# trashotron-slimezistor.net
KiCad netlist of a schematic drawn in EAGLE
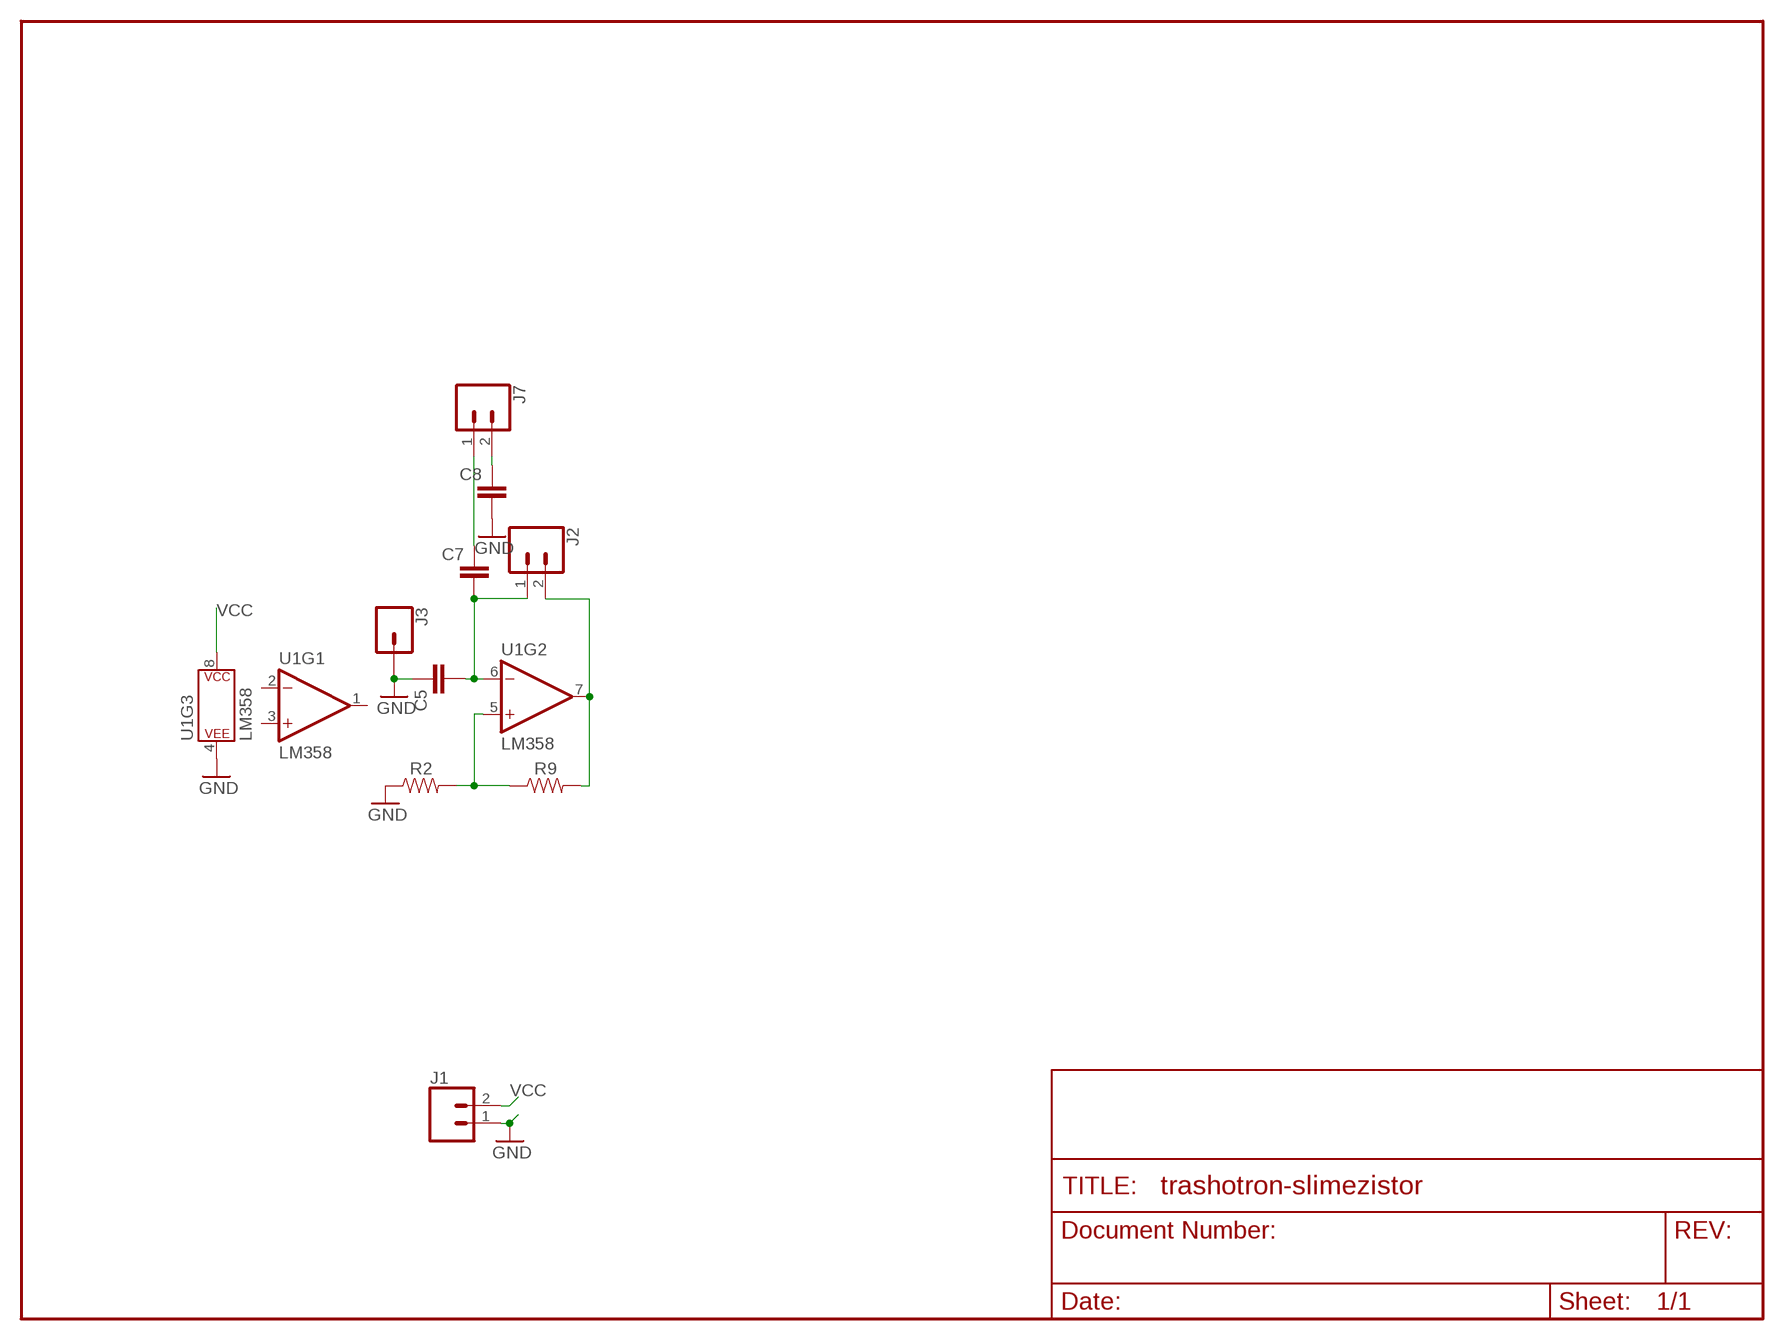
[diagram p0: schematic, sheet 1]

(export (version "E")
  (design (tool "Eeschema 10.0.6"))
  (components
    (comp (ref "C5")
      (value "C-EU050-050X075")
      (footprint "eagle-import:C050-050X075")
      (libsource (lib "eagle-import") (part "C-EU050-050X075"))
    )
    (comp (ref "C7")
      (value "C-EU050-050X075")
      (footprint "eagle-import:C050-050X075")
      (libsource (lib "eagle-import") (part "C-EU050-050X075"))
    )
    (comp (ref "C8")
      (value "C-EU050-050X075")
      (footprint "eagle-import:C050-050X075")
      (libsource (lib "eagle-import") (part "C-EU050-050X075"))
    )
    (comp (ref "J1")
      (value "CONN_02")
      (footprint "eagle-import:1X02")
      (libsource (lib "eagle-import") (part "CONN_02"))
    )
    (comp (ref "J2")
      (value "CONN_02")
      (footprint "eagle-import:1X02")
      (libsource (lib "eagle-import") (part "CONN_02"))
    )
    (comp (ref "J3")
      (value "CONN_01")
      (footprint "eagle-import:1X01")
      (libsource (lib "eagle-import") (part "CONN_01"))
    )
    (comp (ref "J7")
      (value "CONN_02")
      (footprint "eagle-import:1X02")
      (libsource (lib "eagle-import") (part "CONN_02"))
    )
    (comp (ref "R2")
      (value "RESISTORAXIAL-0.3")
      (footprint "eagle-import:AXIAL-0.3")
      (libsource (lib "eagle-import") (part "RESISTORAXIAL-0.3"))
    )
    (comp (ref "R9")
      (value "RESISTORAXIAL-0.3")
      (footprint "eagle-import:AXIAL-0.3")
      (libsource (lib "eagle-import") (part "RESISTORAXIAL-0.3"))
    )
    (comp (ref "U1")
      (value "LM358")
      (footprint "eagle-import:DIP08")
      (libsource (lib "eagle-import") (part "LM358"))
    )
  )
  (nets
    (net (code "1") (name "/VCC") (class "Default")
      (node (ref "J1") (pin "2") (pinfunction "2_2") (pintype "passive"))
      (node (ref "U1") (pin "8") (pinfunction "P$V+_8") (pintype "bidirectional"))
    )
    (net (code "2") (name "GND") (class "Default")
      (node (ref "C5") (pin "1") (pinfunction "1_1") (pintype "passive"))
      (node (ref "C8") (pin "2") (pinfunction "2_2") (pintype "passive"))
      (node (ref "J1") (pin "1") (pinfunction "1_1") (pintype "passive"))
      (node (ref "J3") (pin "1") (pinfunction "1_1") (pintype "passive"))
      (node (ref "R2") (pin "P$1") (pinfunction "1_P$1") (pintype "passive"))
      (node (ref "U1") (pin "4") (pinfunction "P$V-_4") (pintype "bidirectional"))
    )
    (net (code "3") (name "Net-(C7-Pad1)") (class "Default")
      (node (ref "C7") (pin "1") (pinfunction "1_1") (pintype "passive"))
      (node (ref "J7") (pin "1") (pinfunction "1_1") (pintype "passive"))
    )
    (net (code "4") (name "Net-(C8-Pad1)") (class "Default")
      (node (ref "C8") (pin "1") (pinfunction "1_1") (pintype "passive"))
      (node (ref "J7") (pin "2") (pinfunction "2_2") (pintype "passive"))
    )
    (net (code "5") (name "Net-(R2-2)") (class "Default")
      (node (ref "R2") (pin "P$2") (pinfunction "2_P$2") (pintype "passive"))
      (node (ref "R9") (pin "P$1") (pinfunction "1_P$1") (pintype "passive"))
      (node (ref "U1") (pin "5") (pinfunction "+IN_5") (pintype "input"))
    )
    (net (code "6") (name "Net-(R9-2)") (class "Default")
      (node (ref "J2") (pin "2") (pinfunction "2_2") (pintype "passive"))
      (node (ref "R9") (pin "P$2") (pinfunction "2_P$2") (pintype "passive"))
      (node (ref "U1") (pin "7") (pinfunction "OUT_7") (pintype "output"))
    )
    (net (code "7") (name "Net-(U1B--IN)") (class "Default")
      (node (ref "C5") (pin "2") (pinfunction "2_2") (pintype "passive"))
      (node (ref "C7") (pin "2") (pinfunction "2_2") (pintype "passive"))
      (node (ref "J2") (pin "1") (pinfunction "1_1") (pintype "passive"))
      (node (ref "U1") (pin "6") (pinfunction "-IN_6") (pintype "input"))
    )
    (net (code "8") (name "unconnected-(U1A-+IN-Pad3)") (class "Default")
      (node (ref "U1") (pin "3") (pinfunction "+IN_3") (pintype "input"))
    )
    (net (code "9") (name "unconnected-(U1A--IN-Pad2)") (class "Default")
      (node (ref "U1") (pin "2") (pinfunction "-IN_2") (pintype "input"))
    )
    (net (code "10") (name "unconnected-(U1A-OUT-Pad1)") (class "Default")
      (node (ref "U1") (pin "1") (pinfunction "OUT_1") (pintype "output"))
    )
  )
)
